# Input_Protection.net
KiCad netlist of a schematic drawn in Altium Designer
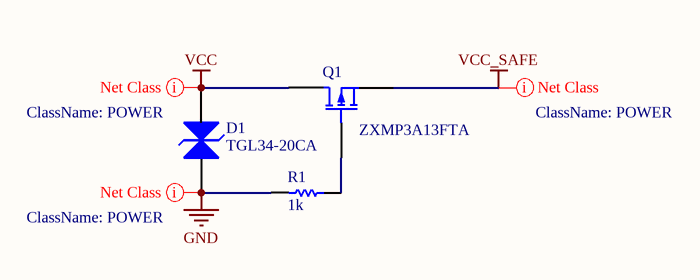
[diagram p0: Input Protection.SchDoc]

(export (version "E")
  (design (tool "Eeschema 10.0.6"))
  (components
    (comp (ref "D1")
      (value "TGL34-20CA")
      (footprint "DIO_MELF_IPC_MD")
      (description "Transil")
      (libsource (lib "agh_racing_2018") (part "TGL34-20CA"))
    )
    (comp (ref "Q1")
      (value "ZXMP3A13FTA")
      (footprint "SOT23_IPC_MD")
      (description "P-mosfet")
      (libsource (lib "agh_racing_2018") (part "ZXMP3A13FTA"))
    )
    (comp (ref "R1")
      (value "1k")
      (footprint "agh_racing_2018:RES_0603_IPC_MD")
      (description "Resistor")
      (fields (field (name "Comment") "Res"))
      (libsource (lib "agh_racing_2018") (part "Res"))
    )
  )
  (nets
    (net (code "1") (name "GND") (class "Default")
      (node (ref "D1") (pin "1") (pinfunction "IN1_1") (pintype "passive"))
      (node (ref "R1") (pin "2") (pinfunction "2_2") (pintype "passive"))
    )
    (net (code "2") (name "Net-(Q1-G)") (class "Default")
      (node (ref "Q1") (pin "1") (pinfunction "G_1") (pintype "passive"))
      (node (ref "R1") (pin "1") (pinfunction "1_1") (pintype "passive"))
    )
    (net (code "3") (name "VCC") (class "Default")
      (node (ref "D1") (pin "2") (pinfunction "IN2_2") (pintype "passive"))
      (node (ref "Q1") (pin "3") (pinfunction "D_3") (pintype "passive"))
    )
    (net (code "4") (name "VCC_SAFE") (class "Default")
      (node (ref "Q1") (pin "2") (pinfunction "S_2") (pintype "passive"))
    )
  )
)
